# osdelux_proto_proc.net
KiCad netlist of a schematic drawn in EAGLE
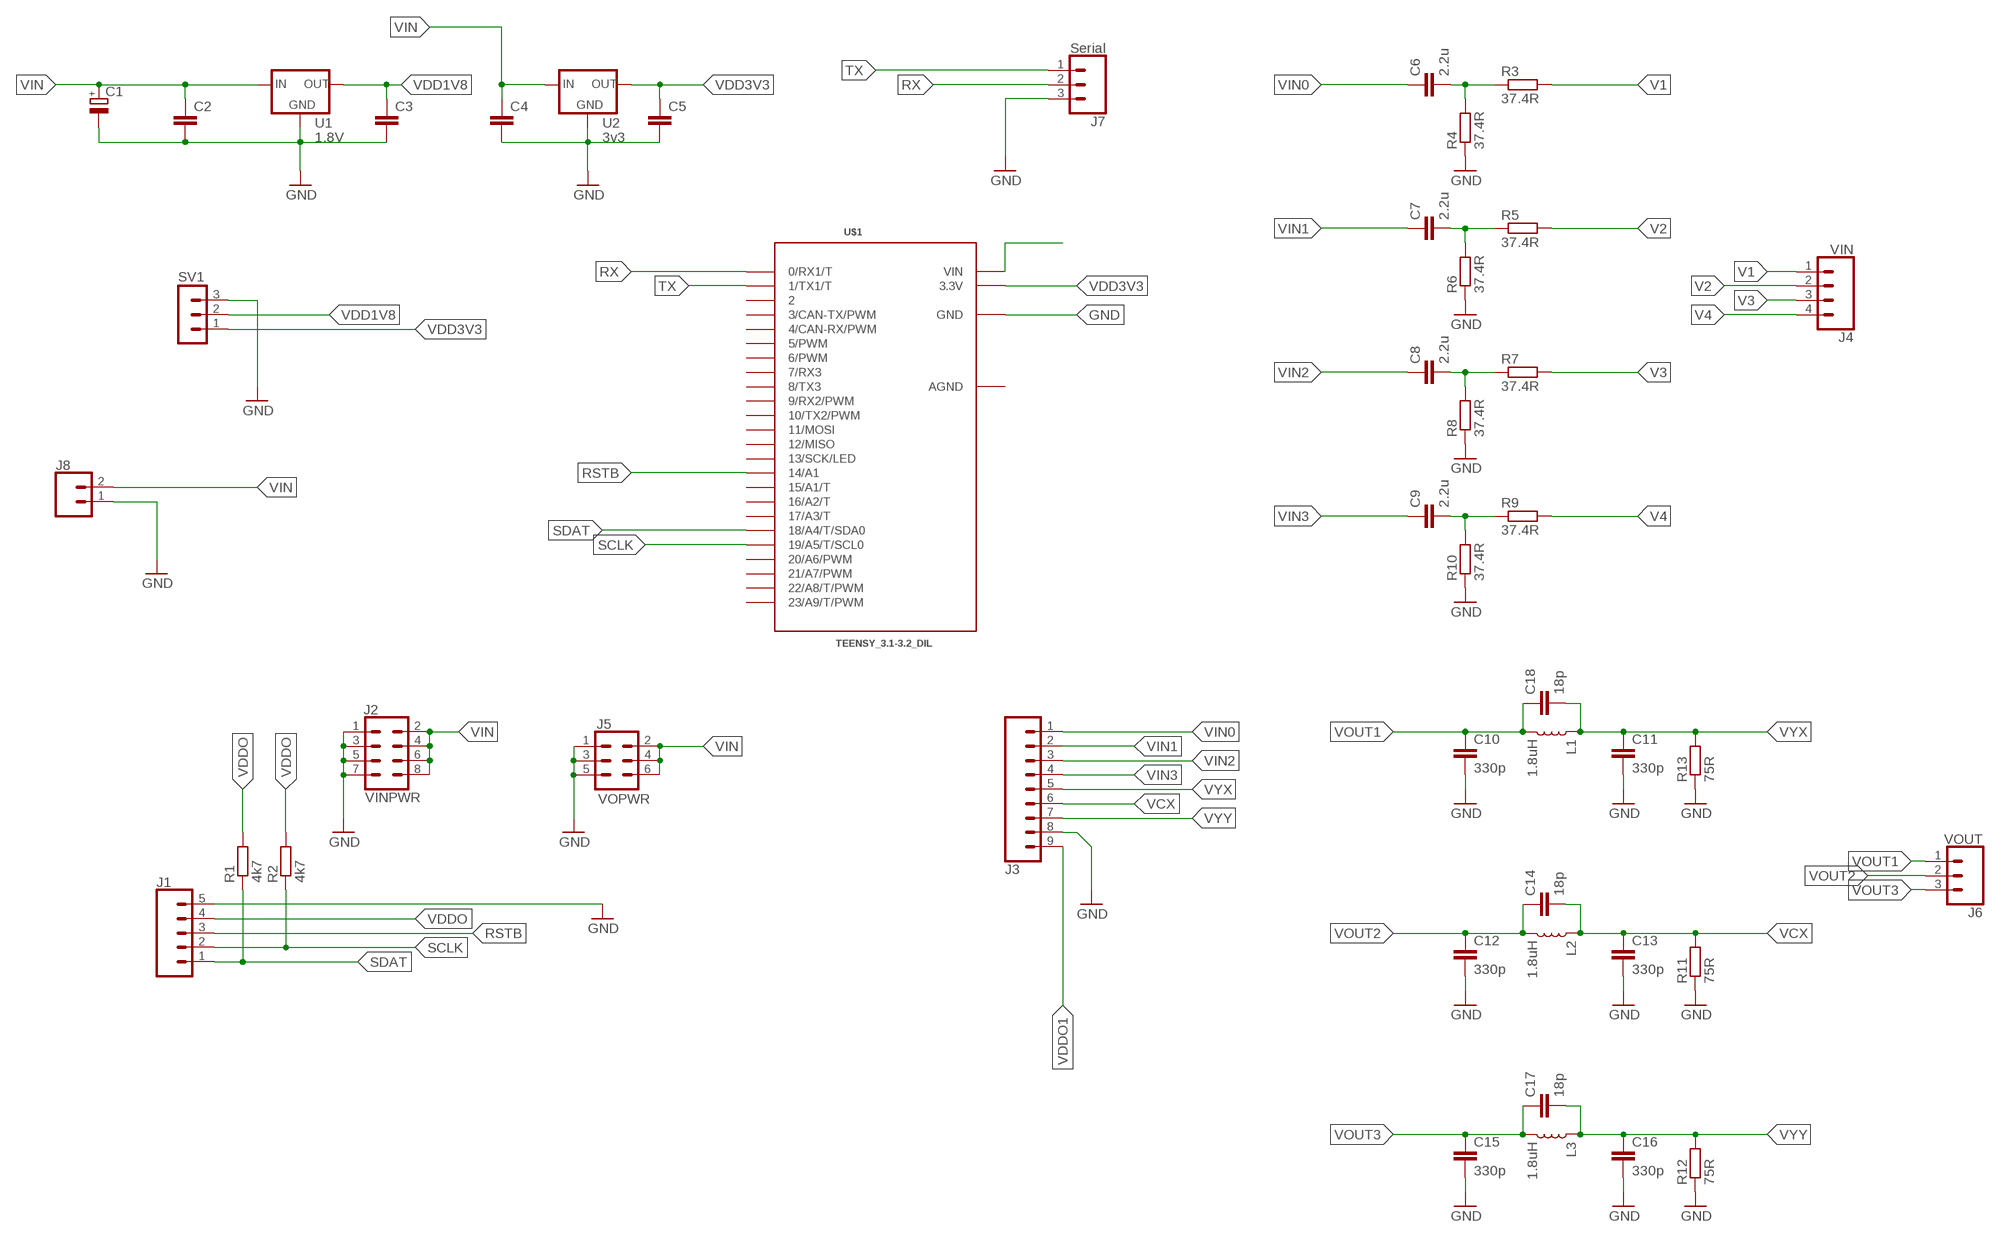
[diagram p0: schematic, sheet 1]

(export (version "E")
  (design (tool "Eeschema 10.0.6"))
  (components
    (comp (ref "C1")
      (value "CPOL-EUE3.5-8")
      (footprint "eagle-import:E3,5-8")
      (libsource (lib "eagle-import") (part "CPOL-EUE3.5-8"))
    )
    (comp (ref "C2")
      (value "C-EUC1206K")
      (footprint "eagle-import:C1206K")
      (libsource (lib "eagle-import") (part "C-EUC1206K"))
    )
    (comp (ref "C3")
      (value "C-EUC1206K")
      (footprint "eagle-import:C1206K")
      (libsource (lib "eagle-import") (part "C-EUC1206K"))
    )
    (comp (ref "C4")
      (value "C-EUC1206K")
      (footprint "eagle-import:C1206K")
      (libsource (lib "eagle-import") (part "C-EUC1206K"))
    )
    (comp (ref "C5")
      (value "C-EUC1206K")
      (footprint "eagle-import:C1206K")
      (libsource (lib "eagle-import") (part "C-EUC1206K"))
    )
    (comp (ref "C6")
      (value "2.2u")
      (footprint "eagle-import:C1206")
      (libsource (lib "eagle-import") (part "C-EUC1206"))
    )
    (comp (ref "C7")
      (value "2.2u")
      (footprint "eagle-import:C1206")
      (libsource (lib "eagle-import") (part "C-EUC1206"))
    )
    (comp (ref "C8")
      (value "2.2u")
      (footprint "eagle-import:C1206")
      (libsource (lib "eagle-import") (part "C-EUC1206"))
    )
    (comp (ref "C9")
      (value "2.2u")
      (footprint "eagle-import:C1206")
      (libsource (lib "eagle-import") (part "C-EUC1206"))
    )
    (comp (ref "C10")
      (value "330p")
      (footprint "eagle-import:C0805")
      (libsource (lib "eagle-import") (part "C-EUC0805"))
    )
    (comp (ref "C11")
      (value "330p")
      (footprint "eagle-import:C0805")
      (libsource (lib "eagle-import") (part "C-EUC0805"))
    )
    (comp (ref "C12")
      (value "330p")
      (footprint "eagle-import:C0805")
      (libsource (lib "eagle-import") (part "C-EUC0805"))
    )
    (comp (ref "C13")
      (value "330p")
      (footprint "eagle-import:C0805")
      (libsource (lib "eagle-import") (part "C-EUC0805"))
    )
    (comp (ref "C14")
      (value "18p")
      (footprint "eagle-import:C0805")
      (libsource (lib "eagle-import") (part "C-EUC0805"))
    )
    (comp (ref "C15")
      (value "330p")
      (footprint "eagle-import:C0805")
      (libsource (lib "eagle-import") (part "C-EUC0805"))
    )
    (comp (ref "C16")
      (value "330p")
      (footprint "eagle-import:C0805")
      (libsource (lib "eagle-import") (part "C-EUC0805"))
    )
    (comp (ref "C17")
      (value "18p")
      (footprint "eagle-import:C0805")
      (libsource (lib "eagle-import") (part "C-EUC0805"))
    )
    (comp (ref "C18")
      (value "18p")
      (footprint "eagle-import:C0805")
      (libsource (lib "eagle-import") (part "C-EUC0805"))
    )
    (comp (ref "J1")
      (value "CONN_05LOCK_LONGPADS")
      (footprint "eagle-import:1X05_LOCK_LONGPADS")
      (libsource (lib "eagle-import") (part "CONN_05LOCK_LONGPADS"))
    )
    (comp (ref "J2")
      (value "VINPWR")
      (footprint "eagle-import:2X4")
      (libsource (lib "eagle-import") (part "CONN_04X2"))
    )
    (comp (ref "J3")
      (value "CONN_09LOCK-LONGPADS")
      (footprint "eagle-import:1X09_LOCK_LONGPADS")
      (libsource (lib "eagle-import") (part "CONN_09LOCK-LONGPADS"))
    )
    (comp (ref "J4")
      (value "VIN")
      (footprint "eagle-import:1X04")
      (libsource (lib "eagle-import") (part "CONN_04"))
    )
    (comp (ref "J5")
      (value "VOPWR")
      (footprint "eagle-import:2X3")
      (libsource (lib "eagle-import") (part "CONN_03X2FEMALE"))
    )
    (comp (ref "J6")
      (value "VOUT")
      (footprint "eagle-import:1X03")
      (libsource (lib "eagle-import") (part "CONN_03"))
    )
    (comp (ref "J7")
      (value "Serial")
      (footprint "eagle-import:1X03")
      (libsource (lib "eagle-import") (part "CONN_03"))
    )
    (comp (ref "J8")
      (value "CONN_02LOCK_LONGPADS")
      (footprint "eagle-import:1X02_LOCK_LONGPADS")
      (libsource (lib "eagle-import") (part "CONN_02LOCK_LONGPADS"))
    )
    (comp (ref "L1")
      (value "1.8uH")
      (footprint "eagle-import:0805")
      (libsource (lib "eagle-import") (part "INDUCTOR-0805-3.3UH"))
    )
    (comp (ref "L2")
      (value "1.8uH")
      (footprint "eagle-import:0805")
      (libsource (lib "eagle-import") (part "INDUCTOR-0805-3.3UH"))
    )
    (comp (ref "L3")
      (value "1.8uH")
      (footprint "eagle-import:0805")
      (libsource (lib "eagle-import") (part "INDUCTOR-0805-3.3UH"))
    )
    (comp (ref "R1")
      (value "4k7")
      (footprint "eagle-import:R0805")
      (libsource (lib "eagle-import") (part "R-EU_R0805"))
    )
    (comp (ref "R2")
      (value "4k7")
      (footprint "eagle-import:R0805")
      (libsource (lib "eagle-import") (part "R-EU_R0805"))
    )
    (comp (ref "R3")
      (value "37.4R")
      (footprint "eagle-import:R0805")
      (libsource (lib "eagle-import") (part "R-EU_R0805"))
    )
    (comp (ref "R4")
      (value "37.4R")
      (footprint "eagle-import:R0805")
      (libsource (lib "eagle-import") (part "R-EU_R0805"))
    )
    (comp (ref "R5")
      (value "37.4R")
      (footprint "eagle-import:R0805")
      (libsource (lib "eagle-import") (part "R-EU_R0805"))
    )
    (comp (ref "R6")
      (value "37.4R")
      (footprint "eagle-import:R0805")
      (libsource (lib "eagle-import") (part "R-EU_R0805"))
    )
    (comp (ref "R7")
      (value "37.4R")
      (footprint "eagle-import:R0805")
      (libsource (lib "eagle-import") (part "R-EU_R0805"))
    )
    (comp (ref "R8")
      (value "37.4R")
      (footprint "eagle-import:R0805")
      (libsource (lib "eagle-import") (part "R-EU_R0805"))
    )
    (comp (ref "R9")
      (value "37.4R")
      (footprint "eagle-import:R0805")
      (libsource (lib "eagle-import") (part "R-EU_R0805"))
    )
    (comp (ref "R10")
      (value "37.4R")
      (footprint "eagle-import:R0805")
      (libsource (lib "eagle-import") (part "R-EU_R0805"))
    )
    (comp (ref "R11")
      (value "75R")
      (footprint "eagle-import:R0805")
      (libsource (lib "eagle-import") (part "R-EU_R0805"))
    )
    (comp (ref "R12")
      (value "75R")
      (footprint "eagle-import:R0805")
      (libsource (lib "eagle-import") (part "R-EU_R0805"))
    )
    (comp (ref "R13")
      (value "75R")
      (footprint "eagle-import:R0805")
      (libsource (lib "eagle-import") (part "R-EU_R0805"))
    )
    (comp (ref "SV1")
      (value "MA03-1")
      (footprint "eagle-import:MA03-1")
      (libsource (lib "eagle-import") (part "MA03-1"))
    )
    (comp (ref "U$1")
      (value "TEENSY_3.1-3.2_DIL")
      (footprint "eagle-import:TEENSY_3.0-3.2&LC_DIL")
      (libsource (lib "eagle-import") (part "TEENSY_3.1-3.2_DIL"))
    )
    (comp (ref "U1")
      (value "1.8V")
      (footprint "eagle-import:DC-DC_CONVERTER_78XX")
      (libsource (lib "eagle-import") (part "R-78E5.0-1.0"))
    )
    (comp (ref "U2")
      (value "3v3")
      (footprint "eagle-import:DC-DC_CONVERTER_78XX")
      (libsource (lib "eagle-import") (part "R-78E5.0-1.0"))
    )
  )
  (nets
    (net (code "1") (name "/AGND") (class "Default")
      (node (ref "U$1") (pin "AGND") (pinfunction "AGND_AGND") (pintype "power_in"))
    )
    (net (code "2") (name "GND") (class "Default")
      (node (ref "C1") (pin "-") (pinfunction "-_-") (pintype "passive"))
      (node (ref "C10") (pin "2") (pinfunction "2_2") (pintype "passive"))
      (node (ref "C11") (pin "2") (pinfunction "2_2") (pintype "passive"))
      (node (ref "C12") (pin "2") (pinfunction "2_2") (pintype "passive"))
      (node (ref "C13") (pin "2") (pinfunction "2_2") (pintype "passive"))
      (node (ref "C15") (pin "2") (pinfunction "2_2") (pintype "passive"))
      (node (ref "C16") (pin "2") (pinfunction "2_2") (pintype "passive"))
      (node (ref "C2") (pin "2") (pinfunction "2_2") (pintype "passive"))
      (node (ref "C3") (pin "2") (pinfunction "2_2") (pintype "passive"))
      (node (ref "C4") (pin "2") (pinfunction "2_2") (pintype "passive"))
      (node (ref "C5") (pin "2") (pinfunction "2_2") (pintype "passive"))
      (node (ref "J1") (pin "5") (pinfunction "5_5") (pintype "passive"))
      (node (ref "J2") (pin "1") (pinfunction "1_1") (pintype "passive"))
      (node (ref "J2") (pin "3") (pinfunction "3_3") (pintype "passive"))
      (node (ref "J2") (pin "5") (pinfunction "5_5") (pintype "passive"))
      (node (ref "J2") (pin "7") (pinfunction "7_7") (pintype "passive"))
      (node (ref "J3") (pin "8") (pinfunction "8_8") (pintype "passive"))
      (node (ref "J5") (pin "1") (pinfunction "1_1") (pintype "bidirectional"))
      (node (ref "J5") (pin "3") (pinfunction "3_3") (pintype "bidirectional"))
      (node (ref "J5") (pin "5") (pinfunction "5_5") (pintype "bidirectional"))
      (node (ref "J7") (pin "3") (pinfunction "3_3") (pintype "passive"))
      (node (ref "J8") (pin "1") (pinfunction "1_1") (pintype "passive"))
      (node (ref "R10") (pin "1") (pinfunction "1_1") (pintype "passive"))
      (node (ref "R11") (pin "1") (pinfunction "1_1") (pintype "passive"))
      (node (ref "R12") (pin "1") (pinfunction "1_1") (pintype "passive"))
      (node (ref "R13") (pin "1") (pinfunction "1_1") (pintype "passive"))
      (node (ref "R4") (pin "1") (pinfunction "1_1") (pintype "passive"))
      (node (ref "R6") (pin "1") (pinfunction "1_1") (pintype "passive"))
      (node (ref "R8") (pin "1") (pinfunction "1_1") (pintype "passive"))
      (node (ref "SV1") (pin "3") (pinfunction "3_3") (pintype "passive"))
      (node (ref "U$1") (pin "GND") (pinfunction "GND_GND") (pintype "power_in"))
      (node (ref "U1") (pin "GND") (pinfunction "GND_GND") (pintype "input"))
      (node (ref "U2") (pin "GND") (pinfunction "GND_GND") (pintype "input"))
    )
    (net (code "3") (name "Net-(C6-Pad2)") (class "Default")
      (node (ref "C6") (pin "2") (pinfunction "2_2") (pintype "passive"))
      (node (ref "R3") (pin "1") (pinfunction "1_1") (pintype "passive"))
      (node (ref "R4") (pin "2") (pinfunction "2_2") (pintype "passive"))
    )
    (net (code "4") (name "Net-(C7-Pad2)") (class "Default")
      (node (ref "C7") (pin "2") (pinfunction "2_2") (pintype "passive"))
      (node (ref "R5") (pin "1") (pinfunction "1_1") (pintype "passive"))
      (node (ref "R6") (pin "2") (pinfunction "2_2") (pintype "passive"))
    )
    (net (code "5") (name "Net-(C8-Pad2)") (class "Default")
      (node (ref "C8") (pin "2") (pinfunction "2_2") (pintype "passive"))
      (node (ref "R7") (pin "1") (pinfunction "1_1") (pintype "passive"))
      (node (ref "R8") (pin "2") (pinfunction "2_2") (pintype "passive"))
    )
    (net (code "6") (name "Net-(C9-Pad2)") (class "Default")
      (node (ref "C9") (pin "2") (pinfunction "2_2") (pintype "passive"))
      (node (ref "R10") (pin "2") (pinfunction "2_2") (pintype "passive"))
      (node (ref "R9") (pin "1") (pinfunction "1_1") (pintype "passive"))
    )
    (net (code "7") (name "RSTB") (class "Default")
      (node (ref "J1") (pin "3") (pinfunction "3_3") (pintype "passive"))
      (node (ref "U$1") (pin "14/A0") (pinfunction "14/A1_14/A0") (pintype "bidirectional"))
    )
    (net (code "8") (name "RX") (class "Default")
      (node (ref "J7") (pin "2") (pinfunction "2_2") (pintype "passive"))
      (node (ref "U$1") (pin "0") (pinfunction "0/RX1/T_0") (pintype "bidirectional"))
    )
    (net (code "9") (name "SCLK") (class "Default")
      (node (ref "J1") (pin "2") (pinfunction "2_2") (pintype "passive"))
      (node (ref "R2") (pin "1") (pinfunction "1_1") (pintype "passive"))
      (node (ref "U$1") (pin "19/A5") (pinfunction "19/A5/T/SCL0_19/A5") (pintype "bidirectional"))
    )
    (net (code "10") (name "SDAT") (class "Default")
      (node (ref "J1") (pin "1") (pinfunction "1_1") (pintype "passive"))
      (node (ref "R1") (pin "1") (pinfunction "1_1") (pintype "passive"))
      (node (ref "U$1") (pin "18/A4") (pinfunction "18/A4/T/SDA0_18/A4") (pintype "bidirectional"))
    )
    (net (code "11") (name "TX") (class "Default")
      (node (ref "J7") (pin "1") (pinfunction "1_1") (pintype "passive"))
      (node (ref "U$1") (pin "1") (pinfunction "1/TX1/T_1") (pintype "bidirectional"))
    )
    (net (code "12") (name "V1") (class "Default")
      (node (ref "J4") (pin "1") (pinfunction "1_1") (pintype "passive"))
      (node (ref "R3") (pin "2") (pinfunction "2_2") (pintype "passive"))
    )
    (net (code "13") (name "V2") (class "Default")
      (node (ref "J4") (pin "2") (pinfunction "2_2") (pintype "passive"))
      (node (ref "R5") (pin "2") (pinfunction "2_2") (pintype "passive"))
    )
    (net (code "14") (name "V3") (class "Default")
      (node (ref "J4") (pin "3") (pinfunction "3_3") (pintype "passive"))
      (node (ref "R7") (pin "2") (pinfunction "2_2") (pintype "passive"))
    )
    (net (code "15") (name "V4") (class "Default")
      (node (ref "J4") (pin "4") (pinfunction "4_4") (pintype "passive"))
      (node (ref "R9") (pin "2") (pinfunction "2_2") (pintype "passive"))
    )
    (net (code "16") (name "VCX") (class "Default")
      (node (ref "C13") (pin "1") (pinfunction "1_1") (pintype "passive"))
      (node (ref "C14") (pin "2") (pinfunction "2_2") (pintype "passive"))
      (node (ref "J3") (pin "6") (pinfunction "6_6") (pintype "passive"))
      (node (ref "L2") (pin "1") (pinfunction "1_1") (pintype "passive"))
      (node (ref "R11") (pin "2") (pinfunction "2_2") (pintype "passive"))
    )
    (net (code "17") (name "VDD1V8") (class "Default")
      (node (ref "C3") (pin "1") (pinfunction "1_1") (pintype "passive"))
      (node (ref "SV1") (pin "2") (pinfunction "2_2") (pintype "passive"))
      (node (ref "U1") (pin "VOUT") (pinfunction "OUT_VOUT") (pintype "passive"))
    )
    (net (code "18") (name "VDD3V3") (class "Default")
      (node (ref "C5") (pin "1") (pinfunction "1_1") (pintype "passive"))
      (node (ref "SV1") (pin "1") (pinfunction "1_1") (pintype "passive"))
      (node (ref "U$1") (pin "3.3V") (pinfunction "3.3V_3.3V") (pintype "power_in"))
      (node (ref "U2") (pin "VOUT") (pinfunction "OUT_VOUT") (pintype "passive"))
    )
    (net (code "19") (name "VDDO") (class "Default")
      (node (ref "J1") (pin "4") (pinfunction "4_4") (pintype "passive"))
      (node (ref "R1") (pin "2") (pinfunction "2_2") (pintype "passive"))
      (node (ref "R2") (pin "2") (pinfunction "2_2") (pintype "passive"))
    )
    (net (code "20") (name "VDDO1") (class "Default")
      (node (ref "J3") (pin "9") (pinfunction "9_9") (pintype "passive"))
    )
    (net (code "21") (name "VIN") (class "Default")
      (node (ref "C1") (pin "+") (pinfunction "+_+") (pintype "passive"))
      (node (ref "C2") (pin "1") (pinfunction "1_1") (pintype "passive"))
      (node (ref "C4") (pin "1") (pinfunction "1_1") (pintype "passive"))
      (node (ref "J2") (pin "2") (pinfunction "2_2") (pintype "passive"))
      (node (ref "J2") (pin "4") (pinfunction "4_4") (pintype "passive"))
      (node (ref "J2") (pin "6") (pinfunction "6_6") (pintype "passive"))
      (node (ref "J2") (pin "8") (pinfunction "8_8") (pintype "passive"))
      (node (ref "J5") (pin "2") (pinfunction "2_2") (pintype "bidirectional"))
      (node (ref "J5") (pin "4") (pinfunction "4_4") (pintype "bidirectional"))
      (node (ref "J5") (pin "6") (pinfunction "6_6") (pintype "bidirectional"))
      (node (ref "J8") (pin "2") (pinfunction "2_2") (pintype "passive"))
      (node (ref "U1") (pin "VIN") (pinfunction "IN_VIN") (pintype "input"))
      (node (ref "U2") (pin "VIN") (pinfunction "IN_VIN") (pintype "input"))
    )
    (net (code "22") (name "VIN0") (class "Default")
      (node (ref "C6") (pin "1") (pinfunction "1_1") (pintype "passive"))
      (node (ref "J3") (pin "1") (pinfunction "1_1") (pintype "passive"))
    )
    (net (code "23") (name "VIN1") (class "Default")
      (node (ref "C7") (pin "1") (pinfunction "1_1") (pintype "passive"))
      (node (ref "J3") (pin "2") (pinfunction "2_2") (pintype "passive"))
    )
    (net (code "24") (name "VIN2") (class "Default")
      (node (ref "C8") (pin "1") (pinfunction "1_1") (pintype "passive"))
      (node (ref "J3") (pin "3") (pinfunction "3_3") (pintype "passive"))
    )
    (net (code "25") (name "VIN3") (class "Default")
      (node (ref "C9") (pin "1") (pinfunction "1_1") (pintype "passive"))
      (node (ref "J3") (pin "4") (pinfunction "4_4") (pintype "passive"))
    )
    (net (code "26") (name "VOUT1") (class "Default")
      (node (ref "C10") (pin "1") (pinfunction "1_1") (pintype "passive"))
      (node (ref "C18") (pin "1") (pinfunction "1_1") (pintype "passive"))
      (node (ref "J6") (pin "1") (pinfunction "1_1") (pintype "passive"))
      (node (ref "L1") (pin "2") (pinfunction "2_2") (pintype "passive"))
    )
    (net (code "27") (name "VOUT2") (class "Default")
      (node (ref "C12") (pin "1") (pinfunction "1_1") (pintype "passive"))
      (node (ref "C14") (pin "1") (pinfunction "1_1") (pintype "passive"))
      (node (ref "J6") (pin "2") (pinfunction "2_2") (pintype "passive"))
      (node (ref "L2") (pin "2") (pinfunction "2_2") (pintype "passive"))
    )
    (net (code "28") (name "VOUT3") (class "Default")
      (node (ref "C15") (pin "1") (pinfunction "1_1") (pintype "passive"))
      (node (ref "C17") (pin "1") (pinfunction "1_1") (pintype "passive"))
      (node (ref "J6") (pin "3") (pinfunction "3_3") (pintype "passive"))
      (node (ref "L3") (pin "2") (pinfunction "2_2") (pintype "passive"))
    )
    (net (code "29") (name "VYX") (class "Default")
      (node (ref "C11") (pin "1") (pinfunction "1_1") (pintype "passive"))
      (node (ref "C18") (pin "2") (pinfunction "2_2") (pintype "passive"))
      (node (ref "J3") (pin "5") (pinfunction "5_5") (pintype "passive"))
      (node (ref "L1") (pin "1") (pinfunction "1_1") (pintype "passive"))
      (node (ref "R13") (pin "2") (pinfunction "2_2") (pintype "passive"))
    )
    (net (code "30") (name "VYY") (class "Default")
      (node (ref "C16") (pin "1") (pinfunction "1_1") (pintype "passive"))
      (node (ref "C17") (pin "2") (pinfunction "2_2") (pintype "passive"))
      (node (ref "J3") (pin "7") (pinfunction "7_7") (pintype "passive"))
      (node (ref "L3") (pin "1") (pinfunction "1_1") (pintype "passive"))
      (node (ref "R12") (pin "2") (pinfunction "2_2") (pintype "passive"))
    )
    (net (code "31") (name "unconnected-(U$1-3{slash}CAN-TX{slash}PWM-Pad3)") (class "Default")
      (node (ref "U$1") (pin "3") (pinfunction "3/CAN-TX/PWM_3") (pintype "bidirectional"))
    )
    (net (code "32") (name "unconnected-(U$1-4{slash}CAN-RX{slash}PWM-Pad4)") (class "Default")
      (node (ref "U$1") (pin "4") (pinfunction "4/CAN-RX/PWM_4") (pintype "bidirectional"))
    )
    (net (code "33") (name "unconnected-(U$1-5{slash}PWM-Pad5)") (class "Default")
      (node (ref "U$1") (pin "5") (pinfunction "5/PWM_5") (pintype "bidirectional"))
    )
    (net (code "34") (name "unconnected-(U$1-6{slash}PWM-Pad6)") (class "Default")
      (node (ref "U$1") (pin "6") (pinfunction "6/PWM_6") (pintype "bidirectional"))
    )
    (net (code "35") (name "unconnected-(U$1-7{slash}RX3-Pad7)") (class "Default")
      (node (ref "U$1") (pin "7") (pinfunction "7/RX3_7") (pintype "bidirectional"))
    )
    (net (code "36") (name "unconnected-(U$1-8{slash}TX3-Pad8)") (class "Default")
      (node (ref "U$1") (pin "8") (pinfunction "8/TX3_8") (pintype "bidirectional"))
    )
    (net (code "37") (name "unconnected-(U$1-9{slash}RX2{slash}PWM-Pad9)") (class "Default")
      (node (ref "U$1") (pin "9") (pinfunction "9/RX2/PWM_9") (pintype "bidirectional"))
    )
    (net (code "38") (name "unconnected-(U$1-10{slash}TX2{slash}PWM-Pad10)") (class "Default")
      (node (ref "U$1") (pin "10") (pinfunction "10/TX2/PWM_10") (pintype "bidirectional"))
    )
    (net (code "39") (name "unconnected-(U$1-11{slash}MOSI-Pad11)") (class "Default")
      (node (ref "U$1") (pin "11") (pinfunction "11/MOSI_11") (pintype "bidirectional"))
    )
    (net (code "40") (name "unconnected-(U$1-12{slash}MISO-Pad12)") (class "Default")
      (node (ref "U$1") (pin "12") (pinfunction "12/MISO_12") (pintype "bidirectional"))
    )
    (net (code "41") (name "unconnected-(U$1-13{slash}SCK{slash}LED-Pad13)") (class "Default")
      (node (ref "U$1") (pin "13") (pinfunction "13/SCK/LED_13") (pintype "bidirectional"))
    )
    (net (code "42") (name "unconnected-(U$1-15{slash}A1{slash}T-Pad15{slash}A1)") (class "Default")
      (node (ref "U$1") (pin "15/A1") (pinfunction "15/A1/T_15/A1") (pintype "bidirectional"))
    )
    (net (code "43") (name "unconnected-(U$1-16{slash}A2{slash}T-Pad16{slash}A2)") (class "Default")
      (node (ref "U$1") (pin "16/A2") (pinfunction "16/A2/T_16/A2") (pintype "bidirectional"))
    )
    (net (code "44") (name "unconnected-(U$1-17{slash}A3{slash}T-Pad17{slash}A3)") (class "Default")
      (node (ref "U$1") (pin "17/A3") (pinfunction "17/A3/T_17/A3") (pintype "bidirectional"))
    )
    (net (code "45") (name "unconnected-(U$1-20{slash}A6{slash}PWM-Pad20{slash}A6)") (class "Default")
      (node (ref "U$1") (pin "20/A6") (pinfunction "20/A6/PWM_20/A6") (pintype "bidirectional"))
    )
    (net (code "46") (name "unconnected-(U$1-21{slash}A7{slash}PWM-Pad21{slash}A7)") (class "Default")
      (node (ref "U$1") (pin "21/A7") (pinfunction "21/A7/PWM_21/A7") (pintype "bidirectional"))
    )
    (net (code "47") (name "unconnected-(U$1-22{slash}A8{slash}T{slash}PWM-Pad22{slash}A8)") (class "Default")
      (node (ref "U$1") (pin "22/A8") (pinfunction "22/A8/T/PWM_22/A8") (pintype "bidirectional"))
    )
    (net (code "48") (name "unconnected-(U$1-23{slash}A9{slash}T{slash}PWM-Pad23{slash}A9)") (class "Default")
      (node (ref "U$1") (pin "23/A9") (pinfunction "23/A9/T/PWM_23/A9") (pintype "bidirectional"))
    )
    (net (code "49") (name "unconnected-(U$1-Pad2)") (class "Default")
      (node (ref "U$1") (pin "2") (pinfunction "2_2") (pintype "bidirectional"))
    )
    (net (code "50") (name "unconnected-(U$1-PadVIN)") (class "Default")
      (node (ref "U$1") (pin "VIN") (pinfunction "VIN_VIN") (pintype "power_in"))
    )
  )
)
